# CU100_V1_0.net
KiCad netlist of a schematic drawn in Altium Designer
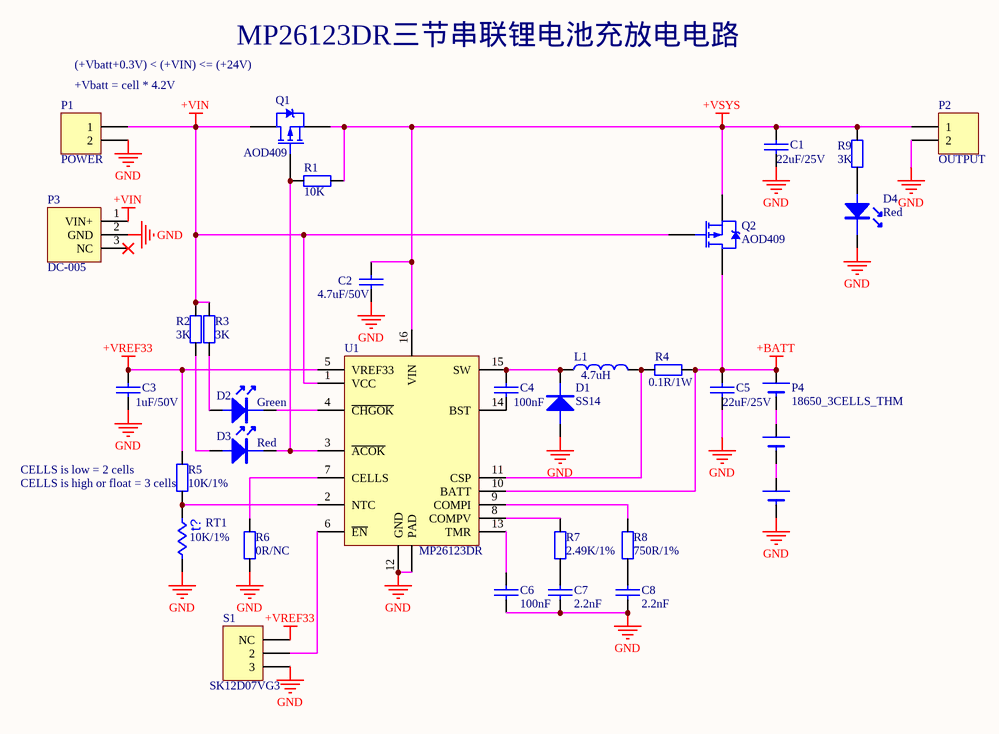
[diagram p0: CU100_V1.0.SchDoc]

(export (version "E")
  (design (tool "Eeschema 10.0.6"))
  (components
    (comp (ref "C1")
      (value "22uF/25V")
      (footprint "Cheng_Resistor_Capacitor:1210_C")
      (libsource (lib "Cheng_Resistor_Capacitor") (part "Cap1"))
    )
    (comp (ref "C2")
      (value "4.7uF/50V")
      (footprint "Cheng_Resistor_Capacitor:1206_C")
      (libsource (lib "Cheng_Resistor_Capacitor") (part "Cap1"))
    )
    (comp (ref "C3")
      (value "1uF/50V")
      (footprint "Cheng_Resistor_Capacitor:0603_CN")
      (libsource (lib "Cheng_Resistor_Capacitor") (part "Cap1"))
    )
    (comp (ref "C4")
      (value "100nF")
      (footprint "Cheng_Resistor_Capacitor:0603_CN")
      (libsource (lib "Cheng_Resistor_Capacitor") (part "Cap1"))
    )
    (comp (ref "C5")
      (value "22uF/25V")
      (footprint "Cheng_Resistor_Capacitor:1210_C")
      (libsource (lib "Cheng_Resistor_Capacitor") (part "Cap1"))
    )
    (comp (ref "C6")
      (value "100nF")
      (footprint "Cheng_Resistor_Capacitor:0603_CN")
      (libsource (lib "Cheng_Resistor_Capacitor") (part "Cap1"))
    )
    (comp (ref "C7")
      (value "2.2nF")
      (footprint "Cheng_Resistor_Capacitor:0603_CN")
      (libsource (lib "Cheng_Resistor_Capacitor") (part "Cap1"))
    )
    (comp (ref "C8")
      (value "2.2nF")
      (footprint "Cheng_Resistor_Capacitor:0603_CN")
      (libsource (lib "Cheng_Resistor_Capacitor") (part "Cap1"))
    )
    (comp (ref "D1")
      (value "SS14")
      (footprint "Cheng_Diode_Transistor:DO-214AC(SMA)")
      (description "SS14,SS24,SS34,M7")
      (libsource (lib "Cheng_Diode_Transistor") (part "Diode-A"))
    )
    (comp (ref "D2")
      (value "Green")
      (footprint "Cheng_Diode_Transistor:0603_LED")
      (libsource (lib "Cheng_Diode_Transistor") (part "LED"))
    )
    (comp (ref "D3")
      (value "Red")
      (footprint "Cheng_Diode_Transistor:0603_LED")
      (libsource (lib "Cheng_Diode_Transistor") (part "LED"))
    )
    (comp (ref "D4")
      (value "Red")
      (footprint "Cheng_Diode_Transistor:0603_LED")
      (libsource (lib "Cheng_Diode_Transistor") (part "LED"))
    )
    (comp (ref "L1")
      (value "4.7uH")
      (footprint "Cheng_Resistor_Capacitor:CDRH104")
      (libsource (lib "Cheng_Resistor_Capacitor") (part "Inductor"))
    )
    (comp (ref "P1")
      (value "POWER")
      (footprint "Cheng_Interface Unit:KF5.08-2P")
      (description "Header, 2-Pin")
      (fields (field (name "PUBLISHER") "Altium Limited"))
      (libsource (lib "") (part "Header 2_1"))
    )
    (comp (ref "P2")
      (value "OUTPUT")
      (footprint "Cheng_Interface Unit:KF5.08-2P")
      (description "Header, 2-Pin")
      (fields (field (name "PUBLISHER") "Altium Limited"))
      (libsource (lib "Cheng_Interface Unit") (part "Header 2"))
    )
    (comp (ref "P3")
      (value "DC-005")
      (footprint "Cheng_Interface Unit:DC-5.5-2.1mm")
      (libsource (lib "Cheng_Interface Unit") (part "DC-005"))
    )
    (comp (ref "P4")
      (value "18650_3CELLS_THM")
      (footprint "Cheng_Interface Unit:18650_3CELLS_THM")
      (libsource (lib "Cheng_Interface Unit") (part "18650_3CELLS_THM"))
    )
    (comp (ref "Q1")
      (value "AOD409")
      (footprint "Cheng_Manostat:TO-252")
      (libsource (lib "Cheng_Diode_Transistor") (part "AOD409"))
    )
    (comp (ref "Q2")
      (value "AOD409")
      (footprint "Cheng_Manostat:TO-252")
      (libsource (lib "Cheng_Diode_Transistor") (part "AOD409"))
    )
    (comp (ref "R1")
      (value "10K")
      (footprint "Cheng_Resistor_Capacitor:0603_RN")
      (libsource (lib "") (part "Res1_1"))
    )
    (comp (ref "R2")
      (value "3K")
      (footprint "Cheng_Resistor_Capacitor:0603_RN")
      (libsource (lib "") (part "Res1_2"))
    )
    (comp (ref "R3")
      (value "3K")
      (footprint "Cheng_Resistor_Capacitor:0603_RN")
      (libsource (lib "Cheng_Resistor_Capacitor") (part "Res1"))
    )
    (comp (ref "R4")
      (value "0.1R/1W")
      (footprint "Cheng_Resistor_Capacitor:2512_R")
      (libsource (lib "") (part "Res1_1"))
    )
    (comp (ref "R5")
      (value "10K/1%")
      (footprint "Cheng_Resistor_Capacitor:0603_RN")
      (libsource (lib "Cheng_Resistor_Capacitor") (part "Res1"))
    )
    (comp (ref "R6")
      (value "0R/NC")
      (footprint "Cheng_Resistor_Capacitor:0603_RN")
      (libsource (lib "Cheng_Resistor_Capacitor") (part "Res1"))
    )
    (comp (ref "R7")
      (value "2.49K/1%")
      (footprint "Cheng_Resistor_Capacitor:0603_RN")
      (libsource (lib "Cheng_Resistor_Capacitor") (part "Res1"))
    )
    (comp (ref "R8")
      (value "750R/1%")
      (footprint "Cheng_Resistor_Capacitor:0603_RN")
      (libsource (lib "Cheng_Resistor_Capacitor") (part "Res1"))
    )
    (comp (ref "R9")
      (value "3K")
      (footprint "Cheng_Resistor_Capacitor:0603_RN")
      (libsource (lib "") (part "Res1_2"))
    )
    (comp (ref "RT1")
      (value "10K/1%")
      (footprint "Cheng_Resistor_Capacitor:RT3950K")
      (description "Thermistor")
      (fields (field (name "PUBLISHER") "Altium Limited"))
      (libsource (lib "Cheng_Resistor_Capacitor") (part "RT"))
    )
    (comp (ref "S1")
      (value "SK12D07VG3")
      (footprint "Cheng_Misc Component:SK12D07VG3")
      (libsource (lib "Cheng_Misc Component") (part "SK12D07VG3"))
    )
    (comp (ref "U1")
      (value "MP26123DR")
      (footprint "Cheng_IC:QFN16(4X4)")
      (libsource (lib "Cheng_Manostat") (part "MP26123DR"))
    )
  )
  (nets
    (net (code "1") (name "+BATT") (class "Default")
      (node (ref "C5") (pin "1") (pinfunction "1_1") (pintype "passive"))
      (node (ref "P4") (pin "1") (pinfunction "+_1") (pintype "passive"))
      (node (ref "Q2") (pin "2") (pinfunction "D_2") (pintype "passive"))
      (node (ref "R4") (pin "2") (pinfunction "2_2") (pintype "passive"))
      (node (ref "U1") (pin "10") (pinfunction "BATT_10") (pintype "passive"))
    )
    (net (code "2") (name "+VIN") (class "Default")
      (node (ref "P1") (pin "1") (pinfunction "1_1") (pintype "passive"))
      (node (ref "P3") (pin "1") (pinfunction "VIN+_1") (pintype "passive"))
      (node (ref "Q1") (pin "2") (pinfunction "D_2") (pintype "passive"))
      (node (ref "Q2") (pin "1") (pinfunction "G_1") (pintype "passive"))
      (node (ref "R2") (pin "1") (pinfunction "1_1") (pintype "passive"))
      (node (ref "R3") (pin "2") (pinfunction "2_2") (pintype "passive"))
      (node (ref "U1") (pin "1") (pinfunction "VCC_1") (pintype "passive"))
    )
    (net (code "3") (name "+VREF33") (class "Default")
      (node (ref "C3") (pin "1") (pinfunction "1_1") (pintype "passive"))
      (node (ref "R5") (pin "2") (pinfunction "2_2") (pintype "passive"))
      (node (ref "S1") (pin "1") (pinfunction "NC_1") (pintype "passive"))
      (node (ref "U1") (pin "5") (pinfunction "VREF33_5") (pintype "passive"))
    )
    (net (code "4") (name "+VSYS") (class "Default")
      (node (ref "C1") (pin "1") (pinfunction "1_1") (pintype "passive"))
      (node (ref "C2") (pin "1") (pinfunction "1_1") (pintype "passive"))
      (node (ref "P2") (pin "1") (pinfunction "1_1") (pintype "passive"))
      (node (ref "Q1") (pin "3") (pinfunction "S_3") (pintype "passive"))
      (node (ref "Q2") (pin "3") (pinfunction "S_3") (pintype "passive"))
      (node (ref "R1") (pin "2") (pinfunction "2_2") (pintype "passive"))
      (node (ref "R9") (pin "1") (pinfunction "1_1") (pintype "passive"))
      (node (ref "U1") (pin "16") (pinfunction "VIN_16") (pintype "passive"))
    )
    (net (code "5") (name "GND") (class "Default")
      (node (ref "C1") (pin "2") (pinfunction "2_2") (pintype "passive"))
      (node (ref "C2") (pin "2") (pinfunction "2_2") (pintype "passive"))
      (node (ref "C3") (pin "2") (pinfunction "2_2") (pintype "passive"))
      (node (ref "C5") (pin "2") (pinfunction "2_2") (pintype "passive"))
      (node (ref "C6") (pin "2") (pinfunction "2_2") (pintype "passive"))
      (node (ref "C7") (pin "2") (pinfunction "2_2") (pintype "passive"))
      (node (ref "C8") (pin "2") (pinfunction "2_2") (pintype "passive"))
      (node (ref "D1") (pin "A") (pinfunction "1_A") (pintype "passive"))
      (node (ref "D4") (pin "K") (pinfunction "2_K") (pintype "passive"))
      (node (ref "P1") (pin "2") (pinfunction "2_2") (pintype "passive"))
      (node (ref "P2") (pin "2") (pinfunction "2_2") (pintype "passive"))
      (node (ref "P3") (pin "2") (pinfunction "GND_2") (pintype "passive"))
      (node (ref "P4") (pin "6") (pinfunction "-_6") (pintype "passive"))
      (node (ref "R6") (pin "1") (pinfunction "1_1") (pintype "passive"))
      (node (ref "RT1") (pin "2") (pinfunction "2_2") (pintype "passive"))
      (node (ref "S1") (pin "3") (pinfunction "3_3") (pintype "passive"))
      (node (ref "U1") (pin "12") (pinfunction "GND_12") (pintype "passive"))
      (node (ref "U1") (pin "PAD") (pinfunction "PAD_PAD") (pintype "passive"))
    )
    (net (code "6") (name "Net-(C7-Pad1)") (class "Default")
      (node (ref "C7") (pin "1") (pinfunction "1_1") (pintype "passive"))
      (node (ref "R7") (pin "1") (pinfunction "1_1") (pintype "passive"))
    )
    (net (code "7") (name "Net-(C8-Pad1)") (class "Default")
      (node (ref "C8") (pin "1") (pinfunction "1_1") (pintype "passive"))
      (node (ref "R8") (pin "1") (pinfunction "1_1") (pintype "passive"))
    )
    (net (code "8") (name "Net-(D1-2)") (class "Default")
      (node (ref "C4") (pin "1") (pinfunction "1_1") (pintype "passive"))
      (node (ref "D1") (pin "K") (pinfunction "2_K") (pintype "passive"))
      (node (ref "L1") (pin "1") (pinfunction "1_1") (pintype "passive"))
      (node (ref "U1") (pin "15") (pinfunction "SW_15") (pintype "passive"))
    )
    (net (code "9") (name "Net-(D2-1)") (class "Default")
      (node (ref "D2") (pin "A") (pinfunction "1_A") (pintype "passive"))
      (node (ref "R3") (pin "1") (pinfunction "1_1") (pintype "passive"))
    )
    (net (code "10") (name "Net-(D2-2)") (class "Default")
      (node (ref "D2") (pin "K") (pinfunction "2_K") (pintype "passive"))
      (node (ref "U1") (pin "4") (pinfunction "~{CHGOK}_4") (pintype "passive"))
    )
    (net (code "11") (name "Net-(D3-1)") (class "Default")
      (node (ref "D3") (pin "A") (pinfunction "1_A") (pintype "passive"))
      (node (ref "R2") (pin "2") (pinfunction "2_2") (pintype "passive"))
    )
    (net (code "12") (name "Net-(D3-2)") (class "Default")
      (node (ref "D3") (pin "K") (pinfunction "2_K") (pintype "passive"))
      (node (ref "Q1") (pin "1") (pinfunction "G_1") (pintype "passive"))
      (node (ref "R1") (pin "1") (pinfunction "1_1") (pintype "passive"))
      (node (ref "U1") (pin "3") (pinfunction "~{ACOK}_3") (pintype "passive"))
    )
    (net (code "13") (name "Net-(D4-1)") (class "Default")
      (node (ref "D4") (pin "A") (pinfunction "1_A") (pintype "passive"))
      (node (ref "R9") (pin "2") (pinfunction "2_2") (pintype "passive"))
    )
    (net (code "14") (name "Net-(P4-+-Pad3)") (class "Default")
      (node (ref "P4") (pin "2") (pinfunction "-_2") (pintype "passive"))
      (node (ref "P4") (pin "3") (pinfunction "+_3") (pintype "passive"))
    )
    (net (code "15") (name "Net-(P4-+-Pad5)") (class "Default")
      (node (ref "P4") (pin "4") (pinfunction "-_4") (pintype "passive"))
      (node (ref "P4") (pin "5") (pinfunction "+_5") (pintype "passive"))
    )
    (net (code "16") (name "Net-(U1-BST)") (class "Default")
      (node (ref "C4") (pin "2") (pinfunction "2_2") (pintype "passive"))
      (node (ref "U1") (pin "14") (pinfunction "BST_14") (pintype "passive"))
    )
    (net (code "17") (name "Net-(U1-CELLS)") (class "Default")
      (node (ref "R6") (pin "2") (pinfunction "2_2") (pintype "passive"))
      (node (ref "U1") (pin "7") (pinfunction "CELLS_7") (pintype "passive"))
    )
    (net (code "18") (name "Net-(U1-COMPI)") (class "Default")
      (node (ref "R8") (pin "2") (pinfunction "2_2") (pintype "passive"))
      (node (ref "U1") (pin "9") (pinfunction "COMPI_9") (pintype "passive"))
    )
    (net (code "19") (name "Net-(U1-COMPV)") (class "Default")
      (node (ref "R7") (pin "2") (pinfunction "2_2") (pintype "passive"))
      (node (ref "U1") (pin "8") (pinfunction "COMPV_8") (pintype "passive"))
    )
    (net (code "20") (name "Net-(U1-CSP)") (class "Default")
      (node (ref "L1") (pin "2") (pinfunction "2_2") (pintype "passive"))
      (node (ref "R4") (pin "1") (pinfunction "1_1") (pintype "passive"))
      (node (ref "U1") (pin "11") (pinfunction "CSP_11") (pintype "passive"))
    )
    (net (code "21") (name "Net-(U1-NTC)") (class "Default")
      (node (ref "R5") (pin "1") (pinfunction "1_1") (pintype "passive"))
      (node (ref "RT1") (pin "1") (pinfunction "1_1") (pintype "passive"))
      (node (ref "U1") (pin "2") (pinfunction "NTC_2") (pintype "passive"))
    )
    (net (code "22") (name "Net-(U1-TMR)") (class "Default")
      (node (ref "C6") (pin "1") (pinfunction "1_1") (pintype "passive"))
      (node (ref "U1") (pin "13") (pinfunction "TMR_13") (pintype "passive"))
    )
    (net (code "23") (name "Net-(U1-~{EN})") (class "Default")
      (node (ref "S1") (pin "2") (pinfunction "2_2") (pintype "passive"))
      (node (ref "U1") (pin "6") (pinfunction "~{EN}_6") (pintype "passive"))
    )
    (net (code "24") (name "unconnected-(P3-NC-Pad3)") (class "Default")
      (node (ref "P3") (pin "3") (pinfunction "NC_3") (pintype "passive+no_connect"))
    )
  )
)
